# Pedal_Board_v0_1.net
KiCad netlist of a schematic drawn in Altium Designer
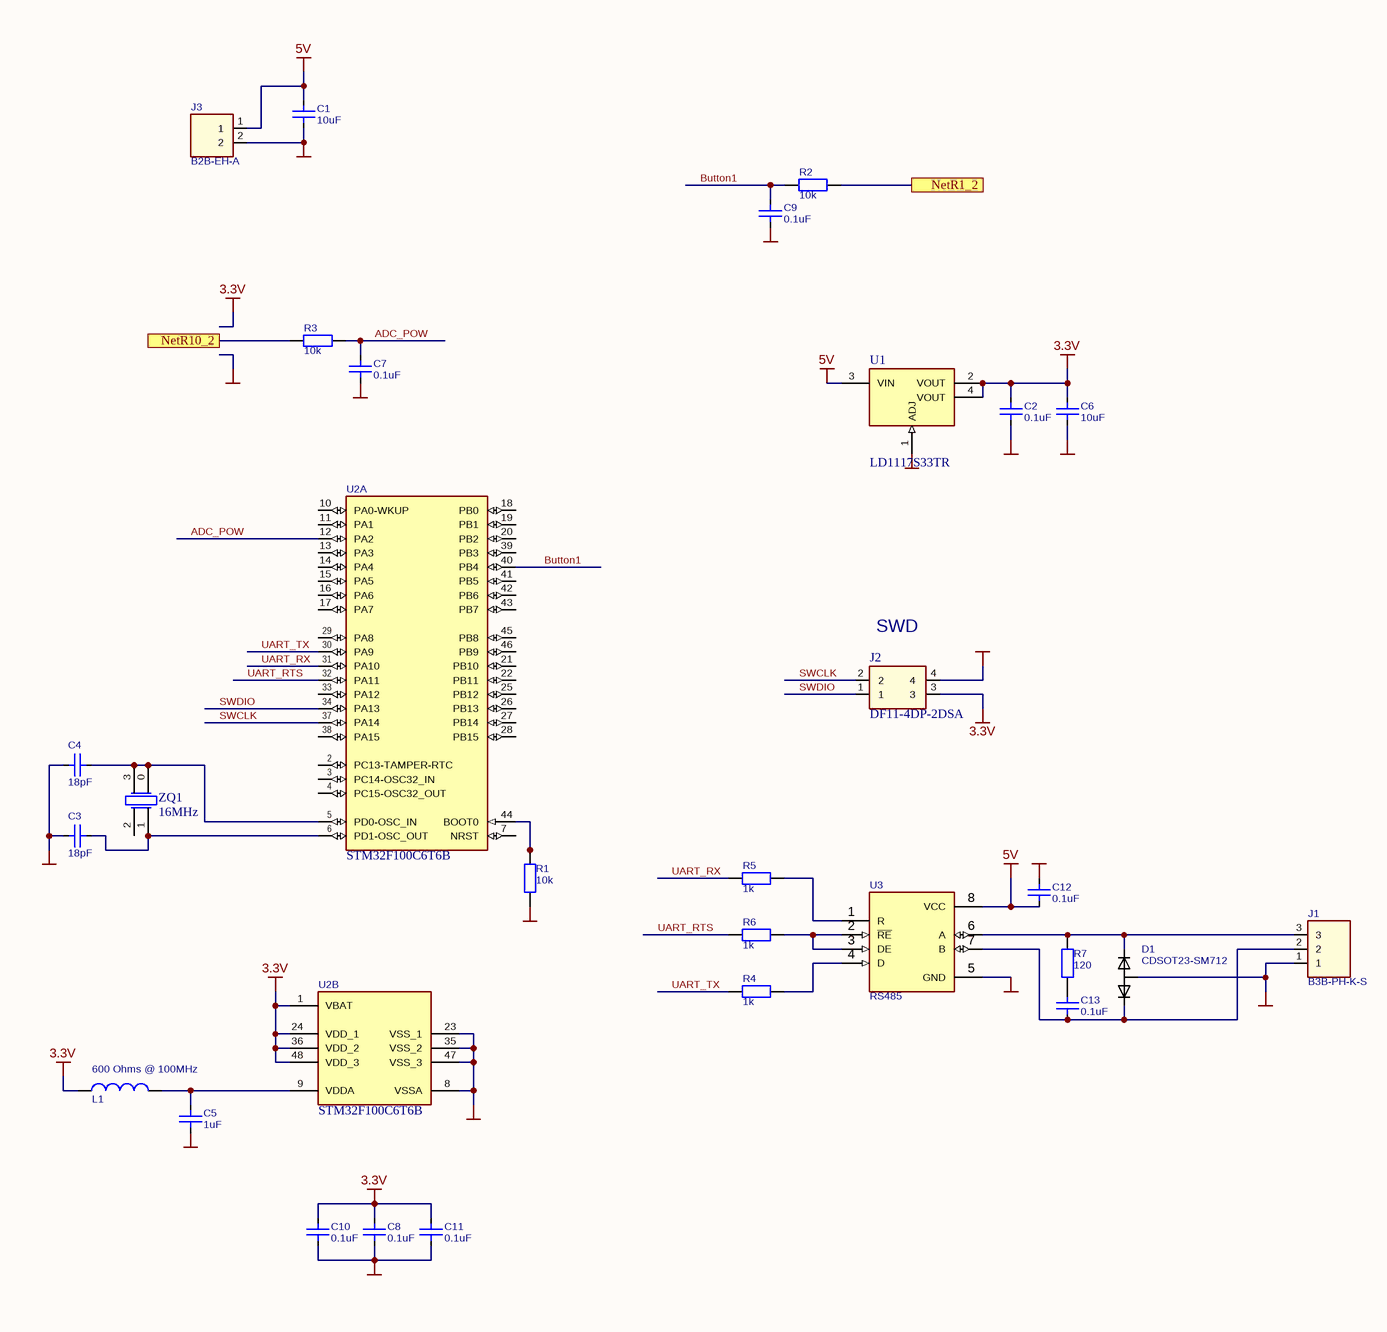
[diagram p0: Pedal Board v0.1.SchDoc]

(export (version "E")
  (design (tool "Eeschema 10.0.6"))
  (components
    (comp (ref "C1")
      (value "10uF")
      (footprint "A_Capacitors:CAPC3216N")
      (description "Capacitor")
      (libsource (lib "A_Capacitors") (part "Cap 3216 (1206)"))
    )
    (comp (ref "C2")
      (value "0.1uF")
      (footprint "A_Capacitors:CAPC1608N")
      (description "Capacitor")
      (libsource (lib "A_Capacitors") (part "Cap 1608 (0603)"))
    )
    (comp (ref "C3")
      (value "18pF")
      (footprint "A_Capacitors:CAPC1608N")
      (description "Capacitor")
      (libsource (lib "A_Capacitors") (part "Cap 1608 (0603)"))
    )
    (comp (ref "C4")
      (value "18pF")
      (footprint "A_Capacitors:CAPC1608N")
      (description "Capacitor")
      (libsource (lib "A_Capacitors") (part "Cap 1608 (0603)"))
    )
    (comp (ref "C5")
      (value "1uF")
      (footprint "A_Capacitors:CAPC1608N")
      (description "Capacitor")
      (libsource (lib "A_Capacitors") (part "Cap 1608 (0603)"))
    )
    (comp (ref "C6")
      (value "10uF")
      (footprint "A_Capacitors:CAPC3216N")
      (description "Capacitor")
      (libsource (lib "A_Capacitors") (part "Cap 3216 (1206)"))
    )
    (comp (ref "C7")
      (value "0.1uF")
      (footprint "A_Capacitors:CAPC1608N")
      (description "Capacitor")
      (libsource (lib "A_Capacitors") (part "Cap 1608 (0603)"))
    )
    (comp (ref "C8")
      (value "0.1uF")
      (footprint "A_Capacitors:CAPC1608N")
      (description "Capacitor")
      (libsource (lib "A_Capacitors") (part "Cap 1608 (0603)"))
    )
    (comp (ref "C9")
      (value "0.1uF")
      (footprint "A_Capacitors:CAPC1608N")
      (description "Capacitor")
      (libsource (lib "A_Capacitors") (part "Cap 1608 (0603)"))
    )
    (comp (ref "C10")
      (value "0.1uF")
      (footprint "A_Capacitors:CAPC1608N")
      (description "Capacitor")
      (libsource (lib "A_Capacitors") (part "Cap 1608 (0603)"))
    )
    (comp (ref "C11")
      (value "0.1uF")
      (footprint "A_Capacitors:CAPC1608N")
      (description "Capacitor")
      (libsource (lib "A_Capacitors") (part "Cap 1608 (0603)"))
    )
    (comp (ref "C12")
      (value "0.1uF")
      (footprint "A_Capacitors:CAPC1608N")
      (description "Capacitor")
      (libsource (lib "A_Capacitors") (part "Cap 1608 (0603)"))
    )
    (comp (ref "C13")
      (value "0.1uF")
      (footprint "A_Capacitors:CAPC1608N")
      (description "Capacitor")
      (libsource (lib "A_Capacitors") (part "Cap 1608 (0603)"))
    )
    (comp (ref "D1")
      (value "CDSOT23-SM712")
      (footprint "A_Diodes:SOT23-3N")
      (description "TVS DIODE 7V/12V 14V/26V SOT23-3")
      (libsource (lib "A_Diodes") (part "CDSOT23-SM712"))
    )
    (comp (ref "J1")
      (value "B3B-PH-K-S")
      (footprint "A_Connectors:B3B-PH-K-S")
      (description "B3B-PH-K-S (JST 2mm)")
      (libsource (lib "A_Connectors") (part "B3B-PH-K-S"))
    )
    (comp (ref "J2")
      (value "DF11-4DP-2DSA")
      (footprint "DF11-4DP-2DSA")
      (libsource (lib "A_Connectors") (part "DF11-4DP-2DSA"))
    )
    (comp (ref "J3")
      (value "B2B-EH-A")
      (footprint "B2B-EH-A")
      (description "B2B-EH-A (JST 2.54mm)")
      (libsource (lib "A_Connectors") (part "B2B-EH-A"))
    )
    (comp (ref "L1")
      (value "600 Ohms @ 100MHz")
      (footprint "A_Inductors:INDC2012N")
      (description "Chip Ferrite Bead BLM21A")
      (libsource (lib "A_Inductors") (part "BLM21A"))
    )
    (comp (ref "R1")
      (value "10k")
      (footprint "A_Resistors:RESC1608N")
      (description "Resistor 1608 (0603)")
      (libsource (lib "A_Resistors") (part "Res 1608 (0603)"))
    )
    (comp (ref "R2")
      (value "10k")
      (footprint "A_Resistors:RESC1608N")
      (description "Resistor 1608 (0603)")
      (libsource (lib "A_Resistors") (part "Res 1608 (0603)"))
    )
    (comp (ref "R3")
      (value "10k")
      (footprint "A_Resistors:RESC1608N")
      (description "Resistor 1608 (0603)")
      (libsource (lib "") (part "Res 1608 (0603)_2"))
    )
    (comp (ref "R4")
      (value "1k")
      (footprint "A_Resistors:RESC1608N")
      (description "Resistor 1608 (0603)")
      (libsource (lib "") (part "Res 1608 (0603)_1"))
    )
    (comp (ref "R5")
      (value "1k")
      (footprint "A_Resistors:RESC1608N")
      (description "Resistor 1608 (0603)")
      (libsource (lib "") (part "Res 1608 (0603)_1"))
    )
    (comp (ref "R6")
      (value "1k")
      (footprint "A_Resistors:RESC1608N")
      (description "Resistor 1608 (0603)")
      (libsource (lib "") (part "Res 1608 (0603)_1"))
    )
    (comp (ref "R7")
      (value "120")
      (footprint "A_Resistors:RESC1608N")
      (description "Resistor 1608 (0603)")
      (libsource (lib "A_Resistors") (part "Res 1608 (0603)"))
    )
    (comp (ref "U1")
      (value "LD1117S33TR")
      (footprint "SOT223-4N")
      (fields (field (name "MANUFACTURER") "Texas Instruments") (field (name "PARTNUMBER") "REG1117"))
      (libsource (lib "A_Voltage_LDO") (part "LM1117MPX-ADJ"))
    )
    (comp (ref "U2")
      (value "STM32F100C6T6B")
      (footprint "STM-LQFP48_N")
      (libsource (lib "A_ICs") (part "STM32F100C6T6B"))
    )
    (comp (ref "U3")
      (value "RS485")
      (footprint "SOIC127P600-8AN")
      (fields (field (name "MANUFACTURER") "Texas Instruments") (field (name "PARTNUMBER") "SN65HVD22P"))
      (libsource (lib "A_ICs") (part "SN65HVD22D"))
    )
    (comp (ref "ZQ1")
      (value "16MHz")
      (footprint "q3225")
      (libsource (lib "A_Miscellaneous") (part "NX3225-4"))
    )
  )
  (nets
    (net (code "1") (name "/ADC_POW") (class "Default")
      (node (ref "C7") (pin "2") (pinfunction "2_2") (pintype "passive"))
      (node (ref "R3") (pin "1") (pinfunction "1_1") (pintype "passive"))
      (node (ref "U2") (pin "12") (pinfunction "PA2_12") (pintype "bidirectional"))
    )
    (net (code "2") (name "/Button1") (class "Default")
      (node (ref "C9") (pin "2") (pinfunction "2_2") (pintype "passive"))
      (node (ref "R2") (pin "1") (pinfunction "1_1") (pintype "passive"))
      (node (ref "U2") (pin "40") (pinfunction "PB4_40") (pintype "bidirectional"))
    )
    (net (code "3") (name "/NetR1_2") (class "Default")
      (node (ref "R2") (pin "2") (pinfunction "2_2") (pintype "passive"))
    )
    (net (code "4") (name "/NetR10_2") (class "Default")
      (node (ref "R3") (pin "2") (pinfunction "2_2") (pintype "passive"))
    )
    (net (code "5") (name "/SWCLK") (class "Default")
      (node (ref "J2") (pin "2") (pinfunction "2_2") (pintype "passive"))
      (node (ref "U2") (pin "37") (pinfunction "PA14_37") (pintype "bidirectional"))
    )
    (net (code "6") (name "/SWDIO") (class "Default")
      (node (ref "J2") (pin "1") (pinfunction "1_1") (pintype "passive"))
      (node (ref "U2") (pin "34") (pinfunction "PA13_34") (pintype "bidirectional"))
    )
    (net (code "7") (name "/UART_RTS") (class "Default")
      (node (ref "R6") (pin "1") (pinfunction "1_1") (pintype "passive"))
      (node (ref "U2") (pin "32") (pinfunction "PA11_32") (pintype "bidirectional"))
    )
    (net (code "8") (name "/UART_RX") (class "Default")
      (node (ref "R5") (pin "1") (pinfunction "1_1") (pintype "passive"))
      (node (ref "U2") (pin "31") (pinfunction "PA10_31") (pintype "bidirectional"))
    )
    (net (code "9") (name "/UART_TX") (class "Default")
      (node (ref "R4") (pin "1") (pinfunction "1_1") (pintype "passive"))
      (node (ref "U2") (pin "30") (pinfunction "PA9_30") (pintype "bidirectional"))
    )
    (net (code "10") (name "3.3V") (class "Default")
      (node (ref "C10") (pin "2") (pinfunction "2_2") (pintype "passive"))
      (node (ref "C11") (pin "2") (pinfunction "2_2") (pintype "passive"))
      (node (ref "C2") (pin "1") (pinfunction "1_1") (pintype "passive"))
      (node (ref "C6") (pin "2") (pinfunction "2_2") (pintype "passive"))
      (node (ref "C8") (pin "2") (pinfunction "2_2") (pintype "passive"))
      (node (ref "J2") (pin "3") (pinfunction "3_3") (pintype "passive"))
      (node (ref "L1") (pin "1") (pinfunction "1_1") (pintype "passive"))
      (node (ref "U1") (pin "2") (pinfunction "VOUT_2") (pintype "power_in"))
      (node (ref "U1") (pin "4") (pinfunction "VOUT_4") (pintype "power_in"))
      (node (ref "U2") (pin "1") (pinfunction "VBAT_1") (pintype "power_in"))
      (node (ref "U2") (pin "24") (pinfunction "VDD_1_24") (pintype "power_in"))
      (node (ref "U2") (pin "36") (pinfunction "VDD_2_36") (pintype "power_in"))
      (node (ref "U2") (pin "48") (pinfunction "VDD_3_48") (pintype "power_in"))
    )
    (net (code "11") (name "5V") (class "Default")
      (node (ref "C1") (pin "2") (pinfunction "2_2") (pintype "passive"))
      (node (ref "C12") (pin "1") (pinfunction "1_1") (pintype "passive"))
      (node (ref "J3") (pin "1") (pinfunction "1_1") (pintype "passive"))
      (node (ref "U1") (pin "3") (pinfunction "VIN_3") (pintype "power_in"))
      (node (ref "U3") (pin "8") (pinfunction "VCC_8") (pintype "power_in"))
    )
    (net (code "12") (name "GND") (class "Default")
      (node (ref "C1") (pin "1") (pinfunction "1_1") (pintype "passive"))
      (node (ref "C10") (pin "1") (pinfunction "1_1") (pintype "passive"))
      (node (ref "C11") (pin "1") (pinfunction "1_1") (pintype "passive"))
      (node (ref "C12") (pin "2") (pinfunction "2_2") (pintype "passive"))
      (node (ref "C2") (pin "2") (pinfunction "2_2") (pintype "passive"))
      (node (ref "C3") (pin "1") (pinfunction "1_1") (pintype "passive"))
      (node (ref "C4") (pin "1") (pinfunction "1_1") (pintype "passive"))
      (node (ref "C5") (pin "1") (pinfunction "1_1") (pintype "passive"))
      (node (ref "C6") (pin "1") (pinfunction "1_1") (pintype "passive"))
      (node (ref "C7") (pin "1") (pinfunction "1_1") (pintype "passive"))
      (node (ref "C8") (pin "1") (pinfunction "1_1") (pintype "passive"))
      (node (ref "C9") (pin "1") (pinfunction "1_1") (pintype "passive"))
      (node (ref "D1") (pin "3") (pinfunction "3_3") (pintype "passive"))
      (node (ref "J1") (pin "1") (pinfunction "1_1") (pintype "passive"))
      (node (ref "J2") (pin "4") (pinfunction "4_4") (pintype "passive"))
      (node (ref "J3") (pin "2") (pinfunction "2_2") (pintype "passive"))
      (node (ref "R1") (pin "1") (pinfunction "1_1") (pintype "passive"))
      (node (ref "U1") (pin "1") (pinfunction "ADJ_1") (pintype "input"))
      (node (ref "U2") (pin "23") (pinfunction "VSS_1_23") (pintype "power_in"))
      (node (ref "U2") (pin "35") (pinfunction "VSS_2_35") (pintype "power_in"))
      (node (ref "U2") (pin "47") (pinfunction "VSS_3_47") (pintype "power_in"))
      (node (ref "U2") (pin "8") (pinfunction "VSSA_8") (pintype "power_in"))
      (node (ref "U3") (pin "5") (pinfunction "GND_5") (pintype "power_in"))
    )
    (net (code "13") (name "Net-(C13-Pad2)") (class "Default")
      (node (ref "C13") (pin "2") (pinfunction "2_2") (pintype "passive"))
      (node (ref "R7") (pin "1") (pinfunction "1_1") (pintype "passive"))
    )
    (net (code "14") (name "Net-(U2A-BOOT0)") (class "Default")
      (node (ref "R1") (pin "2") (pinfunction "2_2") (pintype "passive"))
      (node (ref "U2") (pin "44") (pinfunction "BOOT0_44") (pintype "input"))
    )
    (net (code "15") (name "Net-(U2A-PD0-OSC_IN)") (class "Default")
      (node (ref "C4") (pin "2") (pinfunction "2_2") (pintype "passive"))
      (node (ref "U2") (pin "5") (pinfunction "PD0-OSC_IN_5") (pintype "bidirectional"))
      (node (ref "ZQ1") (pin "0") (pinfunction "OSC1_0") (pintype "passive"))
      (node (ref "ZQ1") (pin "3") (pinfunction "OSC1_3") (pintype "passive"))
    )
    (net (code "16") (name "Net-(U2A-PD1-OSC_OUT)") (class "Default")
      (node (ref "C3") (pin "2") (pinfunction "2_2") (pintype "passive"))
      (node (ref "U2") (pin "6") (pinfunction "PD1-OSC_OUT_6") (pintype "bidirectional"))
      (node (ref "ZQ1") (pin "1") (pinfunction "OSC2_1") (pintype "passive"))
    )
    (net (code "17") (name "Net-(U2B-VDDA)") (class "Default")
      (node (ref "C5") (pin "2") (pinfunction "2_2") (pintype "passive"))
      (node (ref "L1") (pin "2") (pinfunction "2_2") (pintype "passive"))
      (node (ref "U2") (pin "9") (pinfunction "VDDA_9") (pintype "power_in"))
    )
    (net (code "18") (name "Net-(U3-A)") (class "Default")
      (node (ref "D1") (pin "2") (pinfunction "2_2") (pintype "passive"))
      (node (ref "J1") (pin "3") (pinfunction "3_3") (pintype "passive"))
      (node (ref "R7") (pin "2") (pinfunction "2_2") (pintype "passive"))
      (node (ref "U3") (pin "6") (pinfunction "A_6") (pintype "bidirectional"))
    )
    (net (code "19") (name "Net-(U3-B)") (class "Default")
      (node (ref "C13") (pin "1") (pinfunction "1_1") (pintype "passive"))
      (node (ref "D1") (pin "1") (pinfunction "1_1") (pintype "power_in"))
      (node (ref "J1") (pin "2") (pinfunction "2_2") (pintype "passive"))
      (node (ref "U3") (pin "7") (pinfunction "B_7") (pintype "bidirectional"))
    )
    (net (code "20") (name "Net-(U3-D)") (class "Default")
      (node (ref "R4") (pin "2") (pinfunction "2_2") (pintype "passive"))
      (node (ref "U3") (pin "4") (pinfunction "D_4") (pintype "input"))
    )
    (net (code "21") (name "Net-(U3-DE)") (class "Default")
      (node (ref "R6") (pin "2") (pinfunction "2_2") (pintype "passive"))
      (node (ref "U3") (pin "2") (pinfunction "~{RE}_2") (pintype "input"))
      (node (ref "U3") (pin "3") (pinfunction "DE_3") (pintype "input"))
    )
    (net (code "22") (name "Net-(U3-R)") (class "Default")
      (node (ref "R5") (pin "2") (pinfunction "2_2") (pintype "passive"))
      (node (ref "U3") (pin "1") (pinfunction "R_1") (pintype "tri_state"))
    )
    (net (code "23") (name "unconnected-(U2A-NRST-Pad7)") (class "Default")
      (node (ref "U2") (pin "7") (pinfunction "NRST_7") (pintype "bidirectional"))
    )
    (net (code "24") (name "unconnected-(U2A-PA0-WKUP-Pad10)") (class "Default")
      (node (ref "U2") (pin "10") (pinfunction "PA0-WKUP_10") (pintype "bidirectional"))
    )
    (net (code "25") (name "unconnected-(U2A-PA1-Pad11)") (class "Default")
      (node (ref "U2") (pin "11") (pinfunction "PA1_11") (pintype "bidirectional"))
    )
    (net (code "26") (name "unconnected-(U2A-PA3-Pad13)") (class "Default")
      (node (ref "U2") (pin "13") (pinfunction "PA3_13") (pintype "bidirectional"))
    )
    (net (code "27") (name "unconnected-(U2A-PA4-Pad14)") (class "Default")
      (node (ref "U2") (pin "14") (pinfunction "PA4_14") (pintype "bidirectional"))
    )
    (net (code "28") (name "unconnected-(U2A-PA5-Pad15)") (class "Default")
      (node (ref "U2") (pin "15") (pinfunction "PA5_15") (pintype "bidirectional"))
    )
    (net (code "29") (name "unconnected-(U2A-PA6-Pad16)") (class "Default")
      (node (ref "U2") (pin "16") (pinfunction "PA6_16") (pintype "bidirectional"))
    )
    (net (code "30") (name "unconnected-(U2A-PA7-Pad17)") (class "Default")
      (node (ref "U2") (pin "17") (pinfunction "PA7_17") (pintype "bidirectional"))
    )
    (net (code "31") (name "unconnected-(U2A-PA8-Pad29)") (class "Default")
      (node (ref "U2") (pin "29") (pinfunction "PA8_29") (pintype "bidirectional"))
    )
    (net (code "32") (name "unconnected-(U2A-PA12-Pad33)") (class "Default")
      (node (ref "U2") (pin "33") (pinfunction "PA12_33") (pintype "bidirectional"))
    )
    (net (code "33") (name "unconnected-(U2A-PA15-Pad38)") (class "Default")
      (node (ref "U2") (pin "38") (pinfunction "PA15_38") (pintype "bidirectional"))
    )
    (net (code "34") (name "unconnected-(U2A-PB0-Pad18)") (class "Default")
      (node (ref "U2") (pin "18") (pinfunction "PB0_18") (pintype "bidirectional"))
    )
    (net (code "35") (name "unconnected-(U2A-PB1-Pad19)") (class "Default")
      (node (ref "U2") (pin "19") (pinfunction "PB1_19") (pintype "bidirectional"))
    )
    (net (code "36") (name "unconnected-(U2A-PB2-Pad20)") (class "Default")
      (node (ref "U2") (pin "20") (pinfunction "PB2_20") (pintype "bidirectional"))
    )
    (net (code "37") (name "unconnected-(U2A-PB3-Pad39)") (class "Default")
      (node (ref "U2") (pin "39") (pinfunction "PB3_39") (pintype "bidirectional"))
    )
    (net (code "38") (name "unconnected-(U2A-PB5-Pad41)") (class "Default")
      (node (ref "U2") (pin "41") (pinfunction "PB5_41") (pintype "bidirectional"))
    )
    (net (code "39") (name "unconnected-(U2A-PB6-Pad42)") (class "Default")
      (node (ref "U2") (pin "42") (pinfunction "PB6_42") (pintype "bidirectional"))
    )
    (net (code "40") (name "unconnected-(U2A-PB7-Pad43)") (class "Default")
      (node (ref "U2") (pin "43") (pinfunction "PB7_43") (pintype "bidirectional"))
    )
    (net (code "41") (name "unconnected-(U2A-PB8-Pad45)") (class "Default")
      (node (ref "U2") (pin "45") (pinfunction "PB8_45") (pintype "bidirectional"))
    )
    (net (code "42") (name "unconnected-(U2A-PB9-Pad46)") (class "Default")
      (node (ref "U2") (pin "46") (pinfunction "PB9_46") (pintype "bidirectional"))
    )
    (net (code "43") (name "unconnected-(U2A-PB10-Pad21)") (class "Default")
      (node (ref "U2") (pin "21") (pinfunction "PB10_21") (pintype "bidirectional"))
    )
    (net (code "44") (name "unconnected-(U2A-PB11-Pad22)") (class "Default")
      (node (ref "U2") (pin "22") (pinfunction "PB11_22") (pintype "bidirectional"))
    )
    (net (code "45") (name "unconnected-(U2A-PB12-Pad25)") (class "Default")
      (node (ref "U2") (pin "25") (pinfunction "PB12_25") (pintype "bidirectional"))
    )
    (net (code "46") (name "unconnected-(U2A-PB13-Pad26)") (class "Default")
      (node (ref "U2") (pin "26") (pinfunction "PB13_26") (pintype "bidirectional"))
    )
    (net (code "47") (name "unconnected-(U2A-PB14-Pad27)") (class "Default")
      (node (ref "U2") (pin "27") (pinfunction "PB14_27") (pintype "bidirectional"))
    )
    (net (code "48") (name "unconnected-(U2A-PB15-Pad28)") (class "Default")
      (node (ref "U2") (pin "28") (pinfunction "PB15_28") (pintype "bidirectional"))
    )
    (net (code "49") (name "unconnected-(U2A-PC13-TAMPER-RTC-Pad2)") (class "Default")
      (node (ref "U2") (pin "2") (pinfunction "PC13-TAMPER-RTC_2") (pintype "bidirectional"))
    )
    (net (code "50") (name "unconnected-(U2A-PC14-OSC32_IN-Pad3)") (class "Default")
      (node (ref "U2") (pin "3") (pinfunction "PC14-OSC32_IN_3") (pintype "bidirectional"))
    )
    (net (code "51") (name "unconnected-(U2A-PC15-OSC32_OUT-Pad4)") (class "Default")
      (node (ref "U2") (pin "4") (pinfunction "PC15-OSC32_OUT_4") (pintype "bidirectional"))
    )
    (net (code "52") (name "unconnected-(ZQ1-OSC2-Pad2)") (class "Default")
      (node (ref "ZQ1") (pin "2") (pinfunction "OSC2_2") (pintype "passive"))
    )
  )
)
